# PCB-VU-SE-2.net
KiCad netlist of a schematic drawn in EAGLE
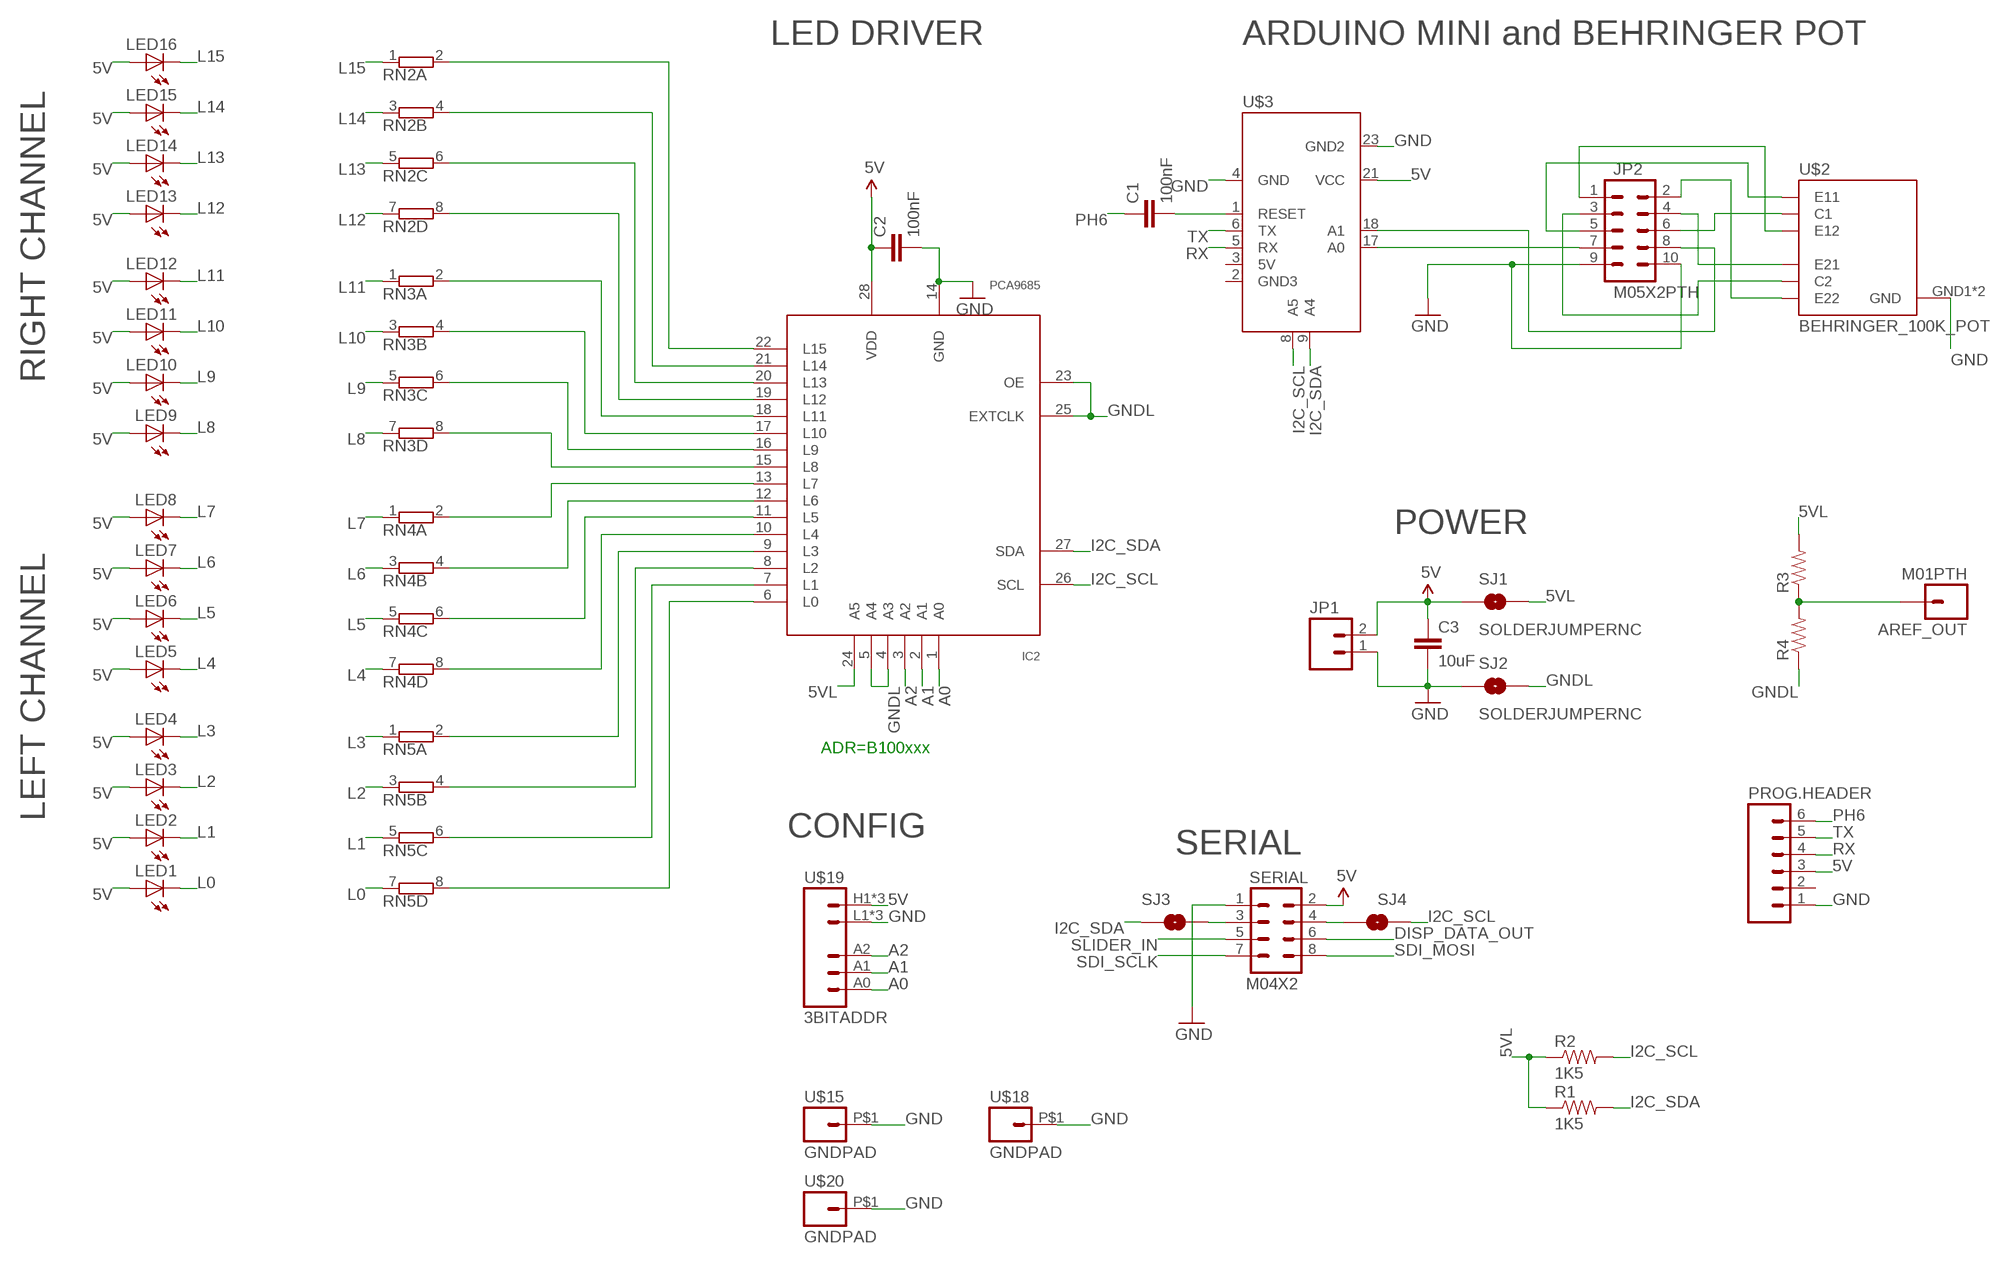
[diagram p0: schematic, sheet 1]

(export (version "E")
  (design (tool "Eeschema 10.0.6"))
  (components
    (comp (ref "AREF_OUT")
      (value "M01PTH")
      (footprint "eagle-import:1X01")
      (libsource (lib "eagle-import") (part "M01PTH"))
    )
    (comp (ref "C1")
      (value "100nF")
      (footprint "eagle-import:0603-CAP")
      (libsource (lib "eagle-import") (part "CAP0603-CAP"))
    )
    (comp (ref "C2")
      (value "100nF")
      (footprint "eagle-import:0603-CAP")
      (libsource (lib "eagle-import") (part "CAP0603-CAP"))
    )
    (comp (ref "C3")
      (value "10uF")
      (footprint "eagle-import:0805")
      (libsource (lib "eagle-import") (part "CAP0805"))
    )
    (comp (ref "IC2")
      (value "PCA9685")
      (footprint "eagle-import:TSSOP28")
      (libsource (lib "eagle-import") (part "PCA9685"))
    )
    (comp (ref "JP1")
      (value "M02PTH")
      (footprint "eagle-import:1X02")
      (libsource (lib "eagle-import") (part "M02PTH"))
    )
    (comp (ref "JP2")
      (value "M05X2PTH")
      (footprint "eagle-import:AVR_ICSP")
      (libsource (lib "eagle-import") (part "M05X2PTH"))
    )
    (comp (ref "LED1")
      (value "LED3MM")
      (footprint "eagle-import:LED3MM")
      (libsource (lib "eagle-import") (part "LED3MM"))
    )
    (comp (ref "LED2")
      (value "LED3MM")
      (footprint "eagle-import:LED3MM")
      (libsource (lib "eagle-import") (part "LED3MM"))
    )
    (comp (ref "LED3")
      (value "LED3MM")
      (footprint "eagle-import:LED3MM")
      (libsource (lib "eagle-import") (part "LED3MM"))
    )
    (comp (ref "LED4")
      (value "LED3MM")
      (footprint "eagle-import:LED3MM")
      (libsource (lib "eagle-import") (part "LED3MM"))
    )
    (comp (ref "LED5")
      (value "LED3MM")
      (footprint "eagle-import:LED3MM")
      (libsource (lib "eagle-import") (part "LED3MM"))
    )
    (comp (ref "LED6")
      (value "LED3MM")
      (footprint "eagle-import:LED3MM")
      (libsource (lib "eagle-import") (part "LED3MM"))
    )
    (comp (ref "LED7")
      (value "LED3MM")
      (footprint "eagle-import:LED3MM")
      (libsource (lib "eagle-import") (part "LED3MM"))
    )
    (comp (ref "LED8")
      (value "LED3MM")
      (footprint "eagle-import:LED3MM")
      (libsource (lib "eagle-import") (part "LED3MM"))
    )
    (comp (ref "LED9")
      (value "LED3MM")
      (footprint "eagle-import:LED3MM")
      (libsource (lib "eagle-import") (part "LED3MM"))
    )
    (comp (ref "LED10")
      (value "LED3MM")
      (footprint "eagle-import:LED3MM")
      (libsource (lib "eagle-import") (part "LED3MM"))
    )
    (comp (ref "LED11")
      (value "LED3MM")
      (footprint "eagle-import:LED3MM")
      (libsource (lib "eagle-import") (part "LED3MM"))
    )
    (comp (ref "LED12")
      (value "LED3MM")
      (footprint "eagle-import:LED3MM")
      (libsource (lib "eagle-import") (part "LED3MM"))
    )
    (comp (ref "LED13")
      (value "LED3MM")
      (footprint "eagle-import:LED3MM")
      (libsource (lib "eagle-import") (part "LED3MM"))
    )
    (comp (ref "LED14")
      (value "LED3MM")
      (footprint "eagle-import:LED3MM")
      (libsource (lib "eagle-import") (part "LED3MM"))
    )
    (comp (ref "LED15")
      (value "LED3MM")
      (footprint "eagle-import:LED3MM")
      (libsource (lib "eagle-import") (part "LED3MM"))
    )
    (comp (ref "LED16")
      (value "LED3MM")
      (footprint "eagle-import:LED3MM")
      (libsource (lib "eagle-import") (part "LED3MM"))
    )
    (comp (ref "PROG.HEADER")
      (value "M06LOCK")
      (footprint "eagle-import:1X06_LOCK")
      (libsource (lib "eagle-import") (part "M06LOCK"))
    )
    (comp (ref "R1")
      (value "1K5")
      (footprint "eagle-import:0603-RES")
      (libsource (lib "eagle-import") (part "RESISTOR0603-RES"))
    )
    (comp (ref "R2")
      (value "1K5")
      (footprint "eagle-import:0603-RES")
      (libsource (lib "eagle-import") (part "RESISTOR0603-RES"))
    )
    (comp (ref "R3")
      (value "RESISTOR0603-RES")
      (footprint "eagle-import:0603-RES")
      (libsource (lib "eagle-import") (part "RESISTOR0603-RES"))
    )
    (comp (ref "R4")
      (value "RESISTOR0603-RES")
      (footprint "eagle-import:0603-RES")
      (libsource (lib "eagle-import") (part "RESISTOR0603-RES"))
    )
    (comp (ref "RN2")
      (value "E4R")
      (footprint "eagle-import:SIL8")
      (libsource (lib "eagle-import") (part "E4R"))
    )
    (comp (ref "RN3")
      (value "E4R")
      (footprint "eagle-import:SIL8")
      (libsource (lib "eagle-import") (part "E4R"))
    )
    (comp (ref "RN4")
      (value "E4R")
      (footprint "eagle-import:SIL8")
      (libsource (lib "eagle-import") (part "E4R"))
    )
    (comp (ref "RN5")
      (value "E4R")
      (footprint "eagle-import:SIL8")
      (libsource (lib "eagle-import") (part "E4R"))
    )
    (comp (ref "SERIAL")
      (value "M04X2")
      (footprint "eagle-import:2X4")
      (libsource (lib "eagle-import") (part "M04X2"))
    )
    (comp (ref "SJ1")
      (value "SOLDERJUMPERNC")
      (footprint "eagle-import:SJ_2S")
      (libsource (lib "eagle-import") (part "SOLDERJUMPERNC"))
    )
    (comp (ref "SJ2")
      (value "SOLDERJUMPERNC")
      (footprint "eagle-import:SJ_2S")
      (libsource (lib "eagle-import") (part "SOLDERJUMPERNC"))
    )
    (comp (ref "SJ3")
      (value "SOLDERJUMPERNC")
      (footprint "eagle-import:SJ_2S")
      (libsource (lib "eagle-import") (part "SOLDERJUMPERNC"))
    )
    (comp (ref "SJ4")
      (value "SOLDERJUMPERNC")
      (footprint "eagle-import:SJ_2S")
      (libsource (lib "eagle-import") (part "SOLDERJUMPERNC"))
    )
    (comp (ref "U$2")
      (value "BEHRINGER_100K_POT")
      (footprint "eagle-import:BEHRINGER_100K_POT")
      (libsource (lib "eagle-import") (part "BEHRINGER_100K_POT"))
    )
    (comp (ref "U$3")
      (value "ARDUINO_MINI_SE1")
      (footprint "eagle-import:ARDUINO_MINI_SE1")
      (libsource (lib "eagle-import") (part "ARDUINO_MINI_SE1"))
    )
    (comp (ref "U$15")
      (value "GNDPAD")
      (footprint "eagle-import:3.2MMPAD")
      (libsource (lib "eagle-import") (part "GNDPAD"))
    )
    (comp (ref "U$18")
      (value "GNDPAD")
      (footprint "eagle-import:3.2MMPAD")
      (libsource (lib "eagle-import") (part "GNDPAD"))
    )
    (comp (ref "U$19")
      (value "3BITADDR")
      (footprint "eagle-import:3BITADDR")
      (libsource (lib "eagle-import") (part "3BITADDR"))
    )
    (comp (ref "U$20")
      (value "GNDPAD")
      (footprint "eagle-import:3.2MMPAD")
      (libsource (lib "eagle-import") (part "GNDPAD"))
    )
  )
  (nets
    (net (code "1") (name "/5VL") (class "Default")
      (node (ref "IC2") (pin "24") (pinfunction "A5_24") (pintype "input"))
      (node (ref "R1") (pin "1") (pinfunction "1_1") (pintype "passive"))
      (node (ref "R2") (pin "1") (pinfunction "1_1") (pintype "passive"))
      (node (ref "R3") (pin "2") (pinfunction "2_2") (pintype "passive"))
      (node (ref "SJ1") (pin "2") (pinfunction "2_2") (pintype "passive"))
    )
    (net (code "2") (name "/A0") (class "Default")
      (node (ref "IC2") (pin "1") (pinfunction "A0_1") (pintype "input"))
      (node (ref "U$19") (pin "A0") (pinfunction "A0_A0") (pintype "passive"))
    )
    (net (code "3") (name "/A1") (class "Default")
      (node (ref "IC2") (pin "2") (pinfunction "A1_2") (pintype "input"))
      (node (ref "U$19") (pin "A1") (pinfunction "A1_A1") (pintype "passive"))
    )
    (net (code "4") (name "/A2") (class "Default")
      (node (ref "IC2") (pin "3") (pinfunction "A2_3") (pintype "input"))
      (node (ref "U$19") (pin "A2") (pinfunction "A2_A2") (pintype "passive"))
    )
    (net (code "5") (name "/DISP_DATA_OUT") (class "Default")
      (node (ref "SERIAL") (pin "6") (pinfunction "6_6") (pintype "passive"))
    )
    (net (code "6") (name "/GNDL") (class "Default")
      (node (ref "IC2") (pin "23") (pinfunction "OE_23") (pintype "input"))
      (node (ref "IC2") (pin "25") (pinfunction "EXTCLK_25") (pintype "input"))
      (node (ref "IC2") (pin "4") (pinfunction "A3_4") (pintype "input"))
      (node (ref "IC2") (pin "5") (pinfunction "A4_5") (pintype "input"))
      (node (ref "R4") (pin "1") (pinfunction "1_1") (pintype "passive"))
      (node (ref "SJ2") (pin "2") (pinfunction "2_2") (pintype "passive"))
    )
    (net (code "7") (name "/I2C_SCL") (class "Default")
      (node (ref "IC2") (pin "26") (pinfunction "SCL_26") (pintype "input"))
      (node (ref "R2") (pin "2") (pinfunction "2_2") (pintype "passive"))
      (node (ref "SJ4") (pin "2") (pinfunction "2_2") (pintype "passive"))
      (node (ref "U$3") (pin "8") (pinfunction "A5_8") (pintype "bidirectional"))
    )
    (net (code "8") (name "/I2C_SDA") (class "Default")
      (node (ref "IC2") (pin "27") (pinfunction "SDA_27") (pintype "input"))
      (node (ref "R1") (pin "2") (pinfunction "2_2") (pintype "passive"))
      (node (ref "SJ3") (pin "1") (pinfunction "1_1") (pintype "passive"))
      (node (ref "U$3") (pin "9") (pinfunction "A4_9") (pintype "bidirectional"))
    )
    (net (code "9") (name "/L0") (class "Default")
      (node (ref "LED1") (pin "K") (pinfunction "C_K") (pintype "passive"))
      (node (ref "RN5") (pin "7") (pinfunction "1_7") (pintype "passive"))
    )
    (net (code "10") (name "/L1") (class "Default")
      (node (ref "LED2") (pin "K") (pinfunction "C_K") (pintype "passive"))
      (node (ref "RN5") (pin "5") (pinfunction "1_5") (pintype "passive"))
    )
    (net (code "11") (name "/L2") (class "Default")
      (node (ref "LED3") (pin "K") (pinfunction "C_K") (pintype "passive"))
      (node (ref "RN5") (pin "3") (pinfunction "1_3") (pintype "passive"))
    )
    (net (code "12") (name "/L3") (class "Default")
      (node (ref "LED4") (pin "K") (pinfunction "C_K") (pintype "passive"))
      (node (ref "RN5") (pin "1") (pinfunction "1_1") (pintype "passive"))
    )
    (net (code "13") (name "/L4") (class "Default")
      (node (ref "LED5") (pin "K") (pinfunction "C_K") (pintype "passive"))
      (node (ref "RN4") (pin "7") (pinfunction "1_7") (pintype "passive"))
    )
    (net (code "14") (name "/L5") (class "Default")
      (node (ref "LED6") (pin "K") (pinfunction "C_K") (pintype "passive"))
      (node (ref "RN4") (pin "5") (pinfunction "1_5") (pintype "passive"))
    )
    (net (code "15") (name "/L6") (class "Default")
      (node (ref "LED7") (pin "K") (pinfunction "C_K") (pintype "passive"))
      (node (ref "RN4") (pin "3") (pinfunction "1_3") (pintype "passive"))
    )
    (net (code "16") (name "/L7") (class "Default")
      (node (ref "LED8") (pin "K") (pinfunction "C_K") (pintype "passive"))
      (node (ref "RN4") (pin "1") (pinfunction "1_1") (pintype "passive"))
    )
    (net (code "17") (name "/L8") (class "Default")
      (node (ref "LED9") (pin "K") (pinfunction "C_K") (pintype "passive"))
      (node (ref "RN3") (pin "7") (pinfunction "1_7") (pintype "passive"))
    )
    (net (code "18") (name "/L9") (class "Default")
      (node (ref "LED10") (pin "K") (pinfunction "C_K") (pintype "passive"))
      (node (ref "RN3") (pin "5") (pinfunction "1_5") (pintype "passive"))
    )
    (net (code "19") (name "/L10") (class "Default")
      (node (ref "LED11") (pin "K") (pinfunction "C_K") (pintype "passive"))
      (node (ref "RN3") (pin "3") (pinfunction "1_3") (pintype "passive"))
    )
    (net (code "20") (name "/L11") (class "Default")
      (node (ref "LED12") (pin "K") (pinfunction "C_K") (pintype "passive"))
      (node (ref "RN3") (pin "1") (pinfunction "1_1") (pintype "passive"))
    )
    (net (code "21") (name "/L12") (class "Default")
      (node (ref "LED13") (pin "K") (pinfunction "C_K") (pintype "passive"))
      (node (ref "RN2") (pin "7") (pinfunction "1_7") (pintype "passive"))
    )
    (net (code "22") (name "/L13") (class "Default")
      (node (ref "LED14") (pin "K") (pinfunction "C_K") (pintype "passive"))
      (node (ref "RN2") (pin "5") (pinfunction "1_5") (pintype "passive"))
    )
    (net (code "23") (name "/L14") (class "Default")
      (node (ref "LED15") (pin "K") (pinfunction "C_K") (pintype "passive"))
      (node (ref "RN2") (pin "3") (pinfunction "1_3") (pintype "passive"))
    )
    (net (code "24") (name "/L15") (class "Default")
      (node (ref "LED16") (pin "K") (pinfunction "C_K") (pintype "passive"))
      (node (ref "RN2") (pin "1") (pinfunction "1_1") (pintype "passive"))
    )
    (net (code "25") (name "/PH6") (class "Default")
      (node (ref "C1") (pin "1") (pinfunction "1_1") (pintype "passive"))
      (node (ref "PROG.HEADER") (pin "6") (pinfunction "6_6") (pintype "passive"))
    )
    (net (code "26") (name "/RX") (class "Default")
      (node (ref "PROG.HEADER") (pin "4") (pinfunction "4_4") (pintype "passive"))
      (node (ref "U$3") (pin "5") (pinfunction "RX_5") (pintype "bidirectional"))
    )
    (net (code "27") (name "/SDI_MOSI") (class "Default")
      (node (ref "SERIAL") (pin "8") (pinfunction "8_8") (pintype "passive"))
    )
    (net (code "28") (name "/SDI_SCLK") (class "Default")
      (node (ref "SERIAL") (pin "7") (pinfunction "7_7") (pintype "passive"))
    )
    (net (code "29") (name "/SLIDER_IN") (class "Default")
      (node (ref "SERIAL") (pin "5") (pinfunction "5_5") (pintype "passive"))
    )
    (net (code "30") (name "/TX") (class "Default")
      (node (ref "PROG.HEADER") (pin "5") (pinfunction "5_5") (pintype "passive"))
      (node (ref "U$3") (pin "6") (pinfunction "TX_6") (pintype "bidirectional"))
    )
    (net (code "31") (name "5V") (class "Default")
      (node (ref "C2") (pin "1") (pinfunction "1_1") (pintype "passive"))
      (node (ref "C3") (pin "1") (pinfunction "1_1") (pintype "passive"))
      (node (ref "IC2") (pin "28") (pinfunction "VDD_28") (pintype "power_in"))
      (node (ref "JP1") (pin "2") (pinfunction "2_2") (pintype "passive"))
      (node (ref "LED1") (pin "A") (pinfunction "A_A") (pintype "passive"))
      (node (ref "LED10") (pin "A") (pinfunction "A_A") (pintype "passive"))
      (node (ref "LED11") (pin "A") (pinfunction "A_A") (pintype "passive"))
      (node (ref "LED12") (pin "A") (pinfunction "A_A") (pintype "passive"))
      (node (ref "LED13") (pin "A") (pinfunction "A_A") (pintype "passive"))
      (node (ref "LED14") (pin "A") (pinfunction "A_A") (pintype "passive"))
      (node (ref "LED15") (pin "A") (pinfunction "A_A") (pintype "passive"))
      (node (ref "LED16") (pin "A") (pinfunction "A_A") (pintype "passive"))
      (node (ref "LED2") (pin "A") (pinfunction "A_A") (pintype "passive"))
      (node (ref "LED3") (pin "A") (pinfunction "A_A") (pintype "passive"))
      (node (ref "LED4") (pin "A") (pinfunction "A_A") (pintype "passive"))
      (node (ref "LED5") (pin "A") (pinfunction "A_A") (pintype "passive"))
      (node (ref "LED6") (pin "A") (pinfunction "A_A") (pintype "passive"))
      (node (ref "LED7") (pin "A") (pinfunction "A_A") (pintype "passive"))
      (node (ref "LED8") (pin "A") (pinfunction "A_A") (pintype "passive"))
      (node (ref "LED9") (pin "A") (pinfunction "A_A") (pintype "passive"))
      (node (ref "PROG.HEADER") (pin "3") (pinfunction "3_3") (pintype "passive"))
      (node (ref "SERIAL") (pin "2") (pinfunction "2_2") (pintype "passive"))
      (node (ref "SJ1") (pin "1") (pinfunction "1_1") (pintype "passive"))
      (node (ref "U$19") (pin "H1") (pinfunction "VCC_H1") (pintype "passive"))
      (node (ref "U$19") (pin "H2") (pinfunction "VCC_H2") (pintype "passive"))
      (node (ref "U$19") (pin "H3") (pinfunction "VCC_H3") (pintype "passive"))
      (node (ref "U$3") (pin "21") (pinfunction "VCC_21") (pintype "bidirectional"))
    )
    (net (code "32") (name "GND") (class "Default")
      (node (ref "C2") (pin "2") (pinfunction "2_2") (pintype "passive"))
      (node (ref "C3") (pin "2") (pinfunction "2_2") (pintype "passive"))
      (node (ref "IC2") (pin "14") (pinfunction "GND_14") (pintype "power_in"))
      (node (ref "JP1") (pin "1") (pinfunction "1_1") (pintype "passive"))
      (node (ref "JP2") (pin "10") (pinfunction "10_10") (pintype "passive"))
      (node (ref "JP2") (pin "9") (pinfunction "9_9") (pintype "passive"))
      (node (ref "PROG.HEADER") (pin "1") (pinfunction "1_1") (pintype "passive"))
      (node (ref "SERIAL") (pin "1") (pinfunction "1_1") (pintype "passive"))
      (node (ref "SJ2") (pin "1") (pinfunction "1_1") (pintype "passive"))
      (node (ref "U$15") (pin "P$1") (pinfunction "1_P$1") (pintype "passive"))
      (node (ref "U$18") (pin "P$1") (pinfunction "1_P$1") (pintype "passive"))
      (node (ref "U$19") (pin "L1") (pinfunction "GND_L1") (pintype "passive"))
      (node (ref "U$19") (pin "L2") (pinfunction "GND_L2") (pintype "passive"))
      (node (ref "U$19") (pin "L3") (pinfunction "GND_L3") (pintype "passive"))
      (node (ref "U$2") (pin "GND1") (pinfunction "GND_GND1") (pintype "power_in"))
      (node (ref "U$2") (pin "GND2") (pinfunction "GND_GND2") (pintype "power_in"))
      (node (ref "U$20") (pin "P$1") (pinfunction "1_P$1") (pintype "passive"))
      (node (ref "U$3") (pin "23") (pinfunction "GND2_23") (pintype "bidirectional"))
      (node (ref "U$3") (pin "4") (pinfunction "GND_4") (pintype "bidirectional"))
    )
    (net (code "33") (name "Net-(AREF_OUT-Pad1)") (class "Default")
      (node (ref "AREF_OUT") (pin "1") (pinfunction "1_1") (pintype "passive"))
      (node (ref "R3") (pin "1") (pinfunction "1_1") (pintype "passive"))
      (node (ref "R4") (pin "2") (pinfunction "2_2") (pintype "passive"))
    )
    (net (code "34") (name "Net-(IC2-L0)") (class "Default")
      (node (ref "IC2") (pin "6") (pinfunction "L0_6") (pintype "output"))
      (node (ref "RN5") (pin "8") (pinfunction "2_8") (pintype "passive"))
    )
    (net (code "35") (name "Net-(IC2-L1)") (class "Default")
      (node (ref "IC2") (pin "7") (pinfunction "L1_7") (pintype "output"))
      (node (ref "RN5") (pin "6") (pinfunction "2_6") (pintype "passive"))
    )
    (net (code "36") (name "Net-(IC2-L2)") (class "Default")
      (node (ref "IC2") (pin "8") (pinfunction "L2_8") (pintype "output"))
      (node (ref "RN5") (pin "4") (pinfunction "2_4") (pintype "passive"))
    )
    (net (code "37") (name "Net-(IC2-L3)") (class "Default")
      (node (ref "IC2") (pin "9") (pinfunction "L3_9") (pintype "output"))
      (node (ref "RN5") (pin "2") (pinfunction "2_2") (pintype "passive"))
    )
    (net (code "38") (name "Net-(IC2-L4)") (class "Default")
      (node (ref "IC2") (pin "10") (pinfunction "L4_10") (pintype "output"))
      (node (ref "RN4") (pin "8") (pinfunction "2_8") (pintype "passive"))
    )
    (net (code "39") (name "Net-(IC2-L5)") (class "Default")
      (node (ref "IC2") (pin "11") (pinfunction "L5_11") (pintype "output"))
      (node (ref "RN4") (pin "6") (pinfunction "2_6") (pintype "passive"))
    )
    (net (code "40") (name "Net-(IC2-L6)") (class "Default")
      (node (ref "IC2") (pin "12") (pinfunction "L6_12") (pintype "output"))
      (node (ref "RN4") (pin "4") (pinfunction "2_4") (pintype "passive"))
    )
    (net (code "41") (name "Net-(IC2-L7)") (class "Default")
      (node (ref "IC2") (pin "13") (pinfunction "L7_13") (pintype "output"))
      (node (ref "RN4") (pin "2") (pinfunction "2_2") (pintype "passive"))
    )
    (net (code "42") (name "Net-(IC2-L8)") (class "Default")
      (node (ref "IC2") (pin "15") (pinfunction "L8_15") (pintype "output"))
      (node (ref "RN3") (pin "8") (pinfunction "2_8") (pintype "passive"))
    )
    (net (code "43") (name "Net-(IC2-L9)") (class "Default")
      (node (ref "IC2") (pin "16") (pinfunction "L9_16") (pintype "output"))
      (node (ref "RN3") (pin "6") (pinfunction "2_6") (pintype "passive"))
    )
    (net (code "44") (name "Net-(IC2-L10)") (class "Default")
      (node (ref "IC2") (pin "17") (pinfunction "L10_17") (pintype "output"))
      (node (ref "RN3") (pin "4") (pinfunction "2_4") (pintype "passive"))
    )
    (net (code "45") (name "Net-(IC2-L11)") (class "Default")
      (node (ref "IC2") (pin "18") (pinfunction "L11_18") (pintype "output"))
      (node (ref "RN3") (pin "2") (pinfunction "2_2") (pintype "passive"))
    )
    (net (code "46") (name "Net-(IC2-L12)") (class "Default")
      (node (ref "IC2") (pin "19") (pinfunction "L12_19") (pintype "output"))
      (node (ref "RN2") (pin "8") (pinfunction "2_8") (pintype "passive"))
    )
    (net (code "47") (name "Net-(IC2-L13)") (class "Default")
      (node (ref "IC2") (pin "20") (pinfunction "L13_20") (pintype "output"))
      (node (ref "RN2") (pin "6") (pinfunction "2_6") (pintype "passive"))
    )
    (net (code "48") (name "Net-(IC2-L14)") (class "Default")
      (node (ref "IC2") (pin "21") (pinfunction "L14_21") (pintype "output"))
      (node (ref "RN2") (pin "4") (pinfunction "2_4") (pintype "passive"))
    )
    (net (code "49") (name "Net-(IC2-L15)") (class "Default")
      (node (ref "IC2") (pin "22") (pinfunction "L15_22") (pintype "output"))
      (node (ref "RN2") (pin "2") (pinfunction "2_2") (pintype "passive"))
    )
    (net (code "50") (name "Net-(SERIAL-Pad3)") (class "Default")
      (node (ref "SERIAL") (pin "3") (pinfunction "3_3") (pintype "passive"))
      (node (ref "SJ3") (pin "2") (pinfunction "2_2") (pintype "passive"))
    )
    (net (code "51") (name "Net-(SERIAL-Pad4)") (class "Default")
      (node (ref "SERIAL") (pin "4") (pinfunction "4_4") (pintype "passive"))
      (node (ref "SJ4") (pin "1") (pinfunction "1_1") (pintype "passive"))
    )
    (net (code "52") (name "Net-(U$2-C1)") (class "Default")
      (node (ref "JP2") (pin "6") (pinfunction "6_6") (pintype "passive"))
      (node (ref "U$2") (pin "PAD1") (pinfunction "C1_PAD1") (pintype "bidirectional"))
    )
    (net (code "53") (name "Net-(U$2-C2)") (class "Default")
      (node (ref "JP2") (pin "3") (pinfunction "3_3") (pintype "passive"))
      (node (ref "U$2") (pin "PAD4") (pinfunction "C2_PAD4") (pintype "bidirectional"))
    )
    (net (code "54") (name "Net-(U$2-E11)") (class "Default")
      (node (ref "JP2") (pin "5") (pinfunction "5_5") (pintype "passive"))
      (node (ref "U$2") (pin "PAD2") (pinfunction "E11_PAD2") (pintype "bidirectional"))
    )
    (net (code "55") (name "Net-(U$2-E12)") (class "Default")
      (node (ref "JP2") (pin "1") (pinfunction "1_1") (pintype "passive"))
      (node (ref "U$2") (pin "PAD6") (pinfunction "E12_PAD6") (pintype "bidirectional"))
    )
    (net (code "56") (name "Net-(U$2-E21)") (class "Default")
      (node (ref "JP2") (pin "4") (pinfunction "4_4") (pintype "passive"))
      (node (ref "U$2") (pin "PAD3") (pinfunction "E21_PAD3") (pintype "bidirectional"))
    )
    (net (code "57") (name "Net-(U$2-E22)") (class "Default")
      (node (ref "JP2") (pin "2") (pinfunction "2_2") (pintype "passive"))
      (node (ref "U$2") (pin "PAD5") (pinfunction "E22_PAD5") (pintype "bidirectional"))
    )
    (net (code "58") (name "Net-(U$3-A0)") (class "Default")
      (node (ref "JP2") (pin "7") (pinfunction "7_7") (pintype "passive"))
      (node (ref "U$3") (pin "17") (pinfunction "A0_17") (pintype "bidirectional"))
    )
    (net (code "59") (name "Net-(U$3-A1)") (class "Default")
      (node (ref "JP2") (pin "8") (pinfunction "8_8") (pintype "passive"))
      (node (ref "U$3") (pin "18") (pinfunction "A1_18") (pintype "bidirectional"))
    )
    (net (code "60") (name "Net-(U$3-RESET)") (class "Default")
      (node (ref "C1") (pin "2") (pinfunction "2_2") (pintype "passive"))
      (node (ref "U$3") (pin "1") (pinfunction "RESET_1") (pintype "bidirectional"))
    )
    (net (code "61") (name "unconnected-(PROG.HEADER-Pad2)") (class "Default")
      (node (ref "PROG.HEADER") (pin "2") (pinfunction "2_2") (pintype "passive"))
    )
    (net (code "62") (name "unconnected-(U$3-5V-Pad3)") (class "Default")
      (node (ref "U$3") (pin "3") (pinfunction "5V_3") (pintype "bidirectional"))
    )
    (net (code "63") (name "unconnected-(U$3-GND3-Pad2)") (class "Default")
      (node (ref "U$3") (pin "2") (pinfunction "GND3_2") (pintype "bidirectional"))
    )
  )
)
